# VCO.net
KiCad netlist of a schematic drawn in EAGLE
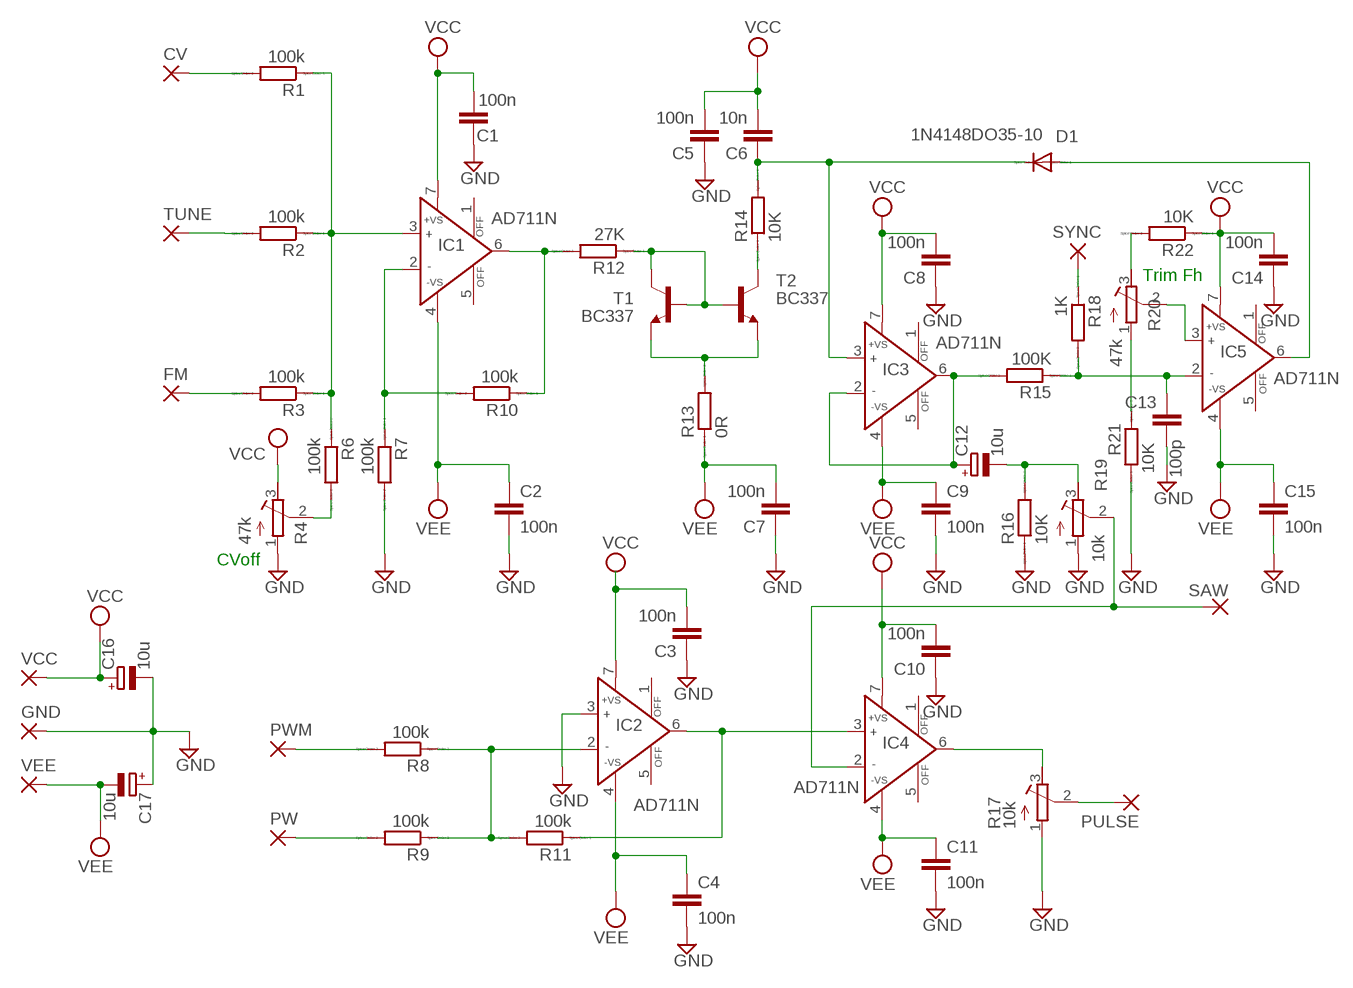
[diagram p0: schematic, sheet 1]

(export (version "E")
  (design (tool "Eeschema 10.0.6"))
  (components
    (comp (ref "C1")
      (value "100n")
      (footprint "eagle-import:C5B2.5")
      (libsource (lib "eagle-import") (part "C5/2.5"))
    )
    (comp (ref "C2")
      (value "100n")
      (footprint "eagle-import:C5B2.5")
      (libsource (lib "eagle-import") (part "C5/2.5"))
    )
    (comp (ref "C3")
      (value "100n")
      (footprint "eagle-import:C5B2.5")
      (libsource (lib "eagle-import") (part "C5/2.5"))
    )
    (comp (ref "C4")
      (value "100n")
      (footprint "eagle-import:C5B2.5")
      (libsource (lib "eagle-import") (part "C5/2.5"))
    )
    (comp (ref "C5")
      (value "100n")
      (footprint "eagle-import:C5B2.5")
      (libsource (lib "eagle-import") (part "C5/2.5"))
    )
    (comp (ref "C6")
      (value "10n")
      (footprint "eagle-import:C5B2.5")
      (libsource (lib "eagle-import") (part "C5/2.5"))
    )
    (comp (ref "C7")
      (value "100n")
      (footprint "eagle-import:C5B2.5")
      (libsource (lib "eagle-import") (part "C5/2.5"))
    )
    (comp (ref "C8")
      (value "100n")
      (footprint "eagle-import:C5B2.5")
      (libsource (lib "eagle-import") (part "C5/2.5"))
    )
    (comp (ref "C9")
      (value "100n")
      (footprint "eagle-import:C5B2.5")
      (libsource (lib "eagle-import") (part "C5/2.5"))
    )
    (comp (ref "C10")
      (value "100n")
      (footprint "eagle-import:C5B2.5")
      (libsource (lib "eagle-import") (part "C5/2.5"))
    )
    (comp (ref "C11")
      (value "100n")
      (footprint "eagle-import:C5B2.5")
      (libsource (lib "eagle-import") (part "C5/2.5"))
    )
    (comp (ref "C12")
      (value "10u")
      (footprint "eagle-import:E2,5-7")
      (libsource (lib "eagle-import") (part "CPOL-EUE2.5-7"))
    )
    (comp (ref "C13")
      (value "100p")
      (footprint "eagle-import:C2.5-2")
      (libsource (lib "eagle-import") (part "C2.5/2"))
    )
    (comp (ref "C14")
      (value "100n")
      (footprint "eagle-import:C5B2.5")
      (libsource (lib "eagle-import") (part "C5/2.5"))
    )
    (comp (ref "C15")
      (value "100n")
      (footprint "eagle-import:C5B2.5")
      (libsource (lib "eagle-import") (part "C5/2.5"))
    )
    (comp (ref "C16")
      (value "10u")
      (footprint "eagle-import:E2,5-7")
      (libsource (lib "eagle-import") (part "CPOL-EUE2.5-7"))
    )
    (comp (ref "C17")
      (value "10u")
      (footprint "eagle-import:E2,5-7")
      (libsource (lib "eagle-import") (part "CPOL-EUE2.5-7"))
    )
    (comp (ref "CV")
      (value "3,17/1,1")
      (footprint "eagle-import:3,17_1,1")
      (libsource (lib "eagle-import") (part "3,17/1,1"))
    )
    (comp (ref "D1")
      (value "1N4148DO35-10")
      (footprint "eagle-import:DO35-10")
      (libsource (lib "eagle-import") (part "1N4148DO35-10"))
    )
    (comp (ref "FM")
      (value "3,17/1,1")
      (footprint "eagle-import:3,17_1,1")
      (libsource (lib "eagle-import") (part "3,17/1,1"))
    )
    (comp (ref "GND")
      (value "3,17/1,1")
      (footprint "eagle-import:3,17_1,1")
      (libsource (lib "eagle-import") (part "3,17/1,1"))
    )
    (comp (ref "IC1")
      (value "AD711N")
      (footprint "eagle-import:DIL08")
      (fields (field (name "MPN") "AD711BQ"))
      (libsource (lib "eagle-import") (part "AD711N"))
    )
    (comp (ref "IC2")
      (value "AD711N")
      (footprint "eagle-import:DIL08")
      (fields (field (name "MPN") "AD711BQ"))
      (libsource (lib "eagle-import") (part "AD711N"))
    )
    (comp (ref "IC3")
      (value "AD711N")
      (footprint "eagle-import:DIL08")
      (fields (field (name "MPN") "AD711BQ"))
      (libsource (lib "eagle-import") (part "AD711N"))
    )
    (comp (ref "IC4")
      (value "AD711N")
      (footprint "eagle-import:DIL08")
      (fields (field (name "MPN") "AD711BQ"))
      (libsource (lib "eagle-import") (part "AD711N"))
    )
    (comp (ref "IC5")
      (value "AD711N")
      (footprint "eagle-import:DIL08")
      (fields (field (name "MPN") "AD711BQ"))
      (libsource (lib "eagle-import") (part "AD711N"))
    )
    (comp (ref "PULSE")
      (value "3,17/1,1")
      (footprint "eagle-import:3,17_1,1")
      (libsource (lib "eagle-import") (part "3,17/1,1"))
    )
    (comp (ref "PW")
      (value "3,17/1,1")
      (footprint "eagle-import:3,17_1,1")
      (libsource (lib "eagle-import") (part "3,17/1,1"))
    )
    (comp (ref "PWM")
      (value "3,17/1,1")
      (footprint "eagle-import:3,17_1,1")
      (libsource (lib "eagle-import") (part "3,17/1,1"))
    )
    (comp (ref "R1")
      (value "100k")
      (footprint "eagle-import:0207_10")
      (fields (field (name "SPICEPREFIX") "27K"))
      (libsource (lib "eagle-import") (part "R0207/10"))
    )
    (comp (ref "R2")
      (value "100k")
      (footprint "eagle-import:0207_10")
      (fields (field (name "SPICEPREFIX") "27K"))
      (libsource (lib "eagle-import") (part "R0207/10"))
    )
    (comp (ref "R3")
      (value "100k")
      (footprint "eagle-import:0207_10")
      (fields (field (name "SPICEPREFIX") "27K"))
      (libsource (lib "eagle-import") (part "R0207/10"))
    )
    (comp (ref "R4")
      (value "47k")
      (footprint "eagle-import:RTRIM64W")
      (libsource (lib "eagle-import") (part "R-TRIMM64W"))
    )
    (comp (ref "R6")
      (value "100k")
      (footprint "eagle-import:0207_10")
      (fields (field (name "SPICEPREFIX") "27K"))
      (libsource (lib "eagle-import") (part "R0207/10"))
    )
    (comp (ref "R7")
      (value "100k")
      (footprint "eagle-import:0207_10")
      (fields (field (name "SPICEPREFIX") "27K"))
      (libsource (lib "eagle-import") (part "R0207/10"))
    )
    (comp (ref "R8")
      (value "100k")
      (footprint "eagle-import:0207_10")
      (fields (field (name "SPICEPREFIX") "27K"))
      (libsource (lib "eagle-import") (part "R0207/10"))
    )
    (comp (ref "R9")
      (value "100k")
      (footprint "eagle-import:0207_10")
      (fields (field (name "SPICEPREFIX") "27K"))
      (libsource (lib "eagle-import") (part "R0207/10"))
    )
    (comp (ref "R10")
      (value "100k")
      (footprint "eagle-import:0207_10")
      (fields (field (name "SPICEPREFIX") "27K"))
      (libsource (lib "eagle-import") (part "R0207/10"))
    )
    (comp (ref "R11")
      (value "100k")
      (footprint "eagle-import:0207_10")
      (fields (field (name "SPICEPREFIX") "27K"))
      (libsource (lib "eagle-import") (part "R0207/10"))
    )
    (comp (ref "R12")
      (value "27K")
      (footprint "eagle-import:0207_10")
      (fields (field (name "SPICEPREFIX") "27K"))
      (libsource (lib "eagle-import") (part "R0207/10"))
    )
    (comp (ref "R13")
      (value "0R")
      (footprint "eagle-import:0207_10")
      (libsource (lib "eagle-import") (part "R0207/10"))
    )
    (comp (ref "R14")
      (value "10K")
      (footprint "eagle-import:0207_10")
      (fields (field (name "SPICEPREFIX") "10K"))
      (libsource (lib "eagle-import") (part "R0207/10"))
    )
    (comp (ref "R15")
      (value "100K")
      (footprint "eagle-import:0207_10")
      (libsource (lib "eagle-import") (part "R0207/10"))
    )
    (comp (ref "R16")
      (value "10K")
      (footprint "eagle-import:0207_10")
      (fields (field (name "SPICEPREFIX") "10K"))
      (libsource (lib "eagle-import") (part "R0207/10"))
    )
    (comp (ref "R17")
      (value "10k")
      (footprint "eagle-import:RTRIM3339P")
      (libsource (lib "eagle-import") (part "resistor_R-TRIMM3339P"))
    )
    (comp (ref "R18")
      (value "1K")
      (footprint "eagle-import:0207_10")
      (libsource (lib "eagle-import") (part "R0207/10"))
    )
    (comp (ref "R19")
      (value "10k")
      (footprint "eagle-import:RTRIM3339P")
      (libsource (lib "eagle-import") (part "resistor_R-TRIMM3339P"))
    )
    (comp (ref "R20")
      (value "47k")
      (footprint "eagle-import:RTRIM64W")
      (libsource (lib "eagle-import") (part "R-TRIMM64W"))
    )
    (comp (ref "R21")
      (value "10K")
      (footprint "eagle-import:0207_10")
      (fields (field (name "SPICEPREFIX") "10K"))
      (libsource (lib "eagle-import") (part "R0207/10"))
    )
    (comp (ref "R22")
      (value "10K")
      (footprint "eagle-import:0207_10")
      (fields (field (name "SPICEPREFIX") "10K"))
      (libsource (lib "eagle-import") (part "R0207/10"))
    )
    (comp (ref "SAW")
      (value "3,17/1,1")
      (footprint "eagle-import:3,17_1,1")
      (libsource (lib "eagle-import") (part "3,17/1,1"))
    )
    (comp (ref "SYNC")
      (value "3,17/1,1")
      (footprint "eagle-import:3,17_1,1")
      (libsource (lib "eagle-import") (part "3,17/1,1"))
    )
    (comp (ref "T1")
      (value "BC337")
      (footprint "eagle-import:TO92")
      (libsource (lib "eagle-import") (part "BC337"))
    )
    (comp (ref "T2")
      (value "BC337")
      (footprint "eagle-import:TO92")
      (libsource (lib "eagle-import") (part "BC337"))
    )
    (comp (ref "TUNE")
      (value "3,17/1,1")
      (footprint "eagle-import:3,17_1,1")
      (libsource (lib "eagle-import") (part "3,17/1,1"))
    )
    (comp (ref "VCC")
      (value "3,17/1,1")
      (footprint "eagle-import:3,17_1,1")
      (libsource (lib "eagle-import") (part "3,17/1,1"))
    )
    (comp (ref "VEE")
      (value "3,17/1,1")
      (footprint "eagle-import:3,17_1,1")
      (libsource (lib "eagle-import") (part "3,17/1,1"))
    )
  )
  (nets
    (net (code "1") (name "GND") (class "Default")
      (node (ref "C1") (pin "1") (pinfunction "1_1") (pintype "passive"))
      (node (ref "C10") (pin "1") (pinfunction "1_1") (pintype "passive"))
      (node (ref "C11") (pin "2") (pinfunction "2_2") (pintype "passive"))
      (node (ref "C13") (pin "1") (pinfunction "1_1") (pintype "passive"))
      (node (ref "C14") (pin "1") (pinfunction "1_1") (pintype "passive"))
      (node (ref "C15") (pin "2") (pinfunction "2_2") (pintype "passive"))
      (node (ref "C16") (pin "-") (pinfunction "-_-") (pintype "passive"))
      (node (ref "C17") (pin "+") (pinfunction "+_+") (pintype "passive"))
      (node (ref "C2") (pin "2") (pinfunction "2_2") (pintype "passive"))
      (node (ref "C3") (pin "1") (pinfunction "1_1") (pintype "passive"))
      (node (ref "C4") (pin "2") (pinfunction "2_2") (pintype "passive"))
      (node (ref "C5") (pin "1") (pinfunction "1_1") (pintype "passive"))
      (node (ref "C7") (pin "1") (pinfunction "1_1") (pintype "passive"))
      (node (ref "C8") (pin "1") (pinfunction "1_1") (pintype "passive"))
      (node (ref "C9") (pin "2") (pinfunction "2_2") (pintype "passive"))
      (node (ref "GND") (pin "1") (pinfunction "P_1") (pintype "passive"))
      (node (ref "IC2") (pin "3") (pinfunction "IN+_3") (pintype "input"))
      (node (ref "R16") (pin "1") (pinfunction "1_1") (pintype "passive"))
      (node (ref "R17") (pin "1") (pinfunction "A_1") (pintype "passive"))
      (node (ref "R19") (pin "1") (pinfunction "A_1") (pintype "passive"))
      (node (ref "R21") (pin "1") (pinfunction "1_1") (pintype "passive"))
      (node (ref "R4") (pin "1") (pinfunction "A_1") (pintype "passive"))
      (node (ref "R7") (pin "2") (pinfunction "2_2") (pintype "passive"))
    )
    (net (code "2") (name "Net-(CV-P)") (class "Default")
      (node (ref "CV") (pin "1") (pinfunction "P_1") (pintype "passive"))
      (node (ref "R1") (pin "2") (pinfunction "2_2") (pintype "passive"))
    )
    (net (code "3") (name "Net-(FM-P)") (class "Default")
      (node (ref "FM") (pin "1") (pinfunction "P_1") (pintype "passive"))
      (node (ref "R3") (pin "2") (pinfunction "2_2") (pintype "passive"))
    )
    (net (code "4") (name "Net-(IC1-IN+)") (class "Default")
      (node (ref "IC1") (pin "3") (pinfunction "IN+_3") (pintype "input"))
      (node (ref "R1") (pin "1") (pinfunction "1_1") (pintype "passive"))
      (node (ref "R2") (pin "1") (pinfunction "1_1") (pintype "passive"))
      (node (ref "R3") (pin "1") (pinfunction "1_1") (pintype "passive"))
      (node (ref "R6") (pin "1") (pinfunction "1_1") (pintype "passive"))
    )
    (net (code "5") (name "Net-(IC1-IN-)") (class "Default")
      (node (ref "IC1") (pin "2") (pinfunction "IN-_2") (pintype "input"))
      (node (ref "R10") (pin "2") (pinfunction "2_2") (pintype "passive"))
      (node (ref "R7") (pin "1") (pinfunction "1_1") (pintype "passive"))
    )
    (net (code "6") (name "Net-(IC1-OUT)") (class "Default")
      (node (ref "IC1") (pin "6") (pinfunction "OUT_6") (pintype "output"))
      (node (ref "R10") (pin "1") (pinfunction "1_1") (pintype "passive"))
      (node (ref "R12") (pin "2") (pinfunction "2_2") (pintype "passive"))
    )
    (net (code "7") (name "Net-(IC2-IN-)") (class "Default")
      (node (ref "IC2") (pin "2") (pinfunction "IN-_2") (pintype "input"))
      (node (ref "R11") (pin "2") (pinfunction "2_2") (pintype "passive"))
      (node (ref "R8") (pin "1") (pinfunction "1_1") (pintype "passive"))
      (node (ref "R9") (pin "1") (pinfunction "1_1") (pintype "passive"))
    )
    (net (code "8") (name "Net-(IC2-OUT)") (class "Default")
      (node (ref "IC2") (pin "6") (pinfunction "OUT_6") (pintype "output"))
      (node (ref "IC4") (pin "3") (pinfunction "IN+_3") (pintype "input"))
      (node (ref "R11") (pin "1") (pinfunction "1_1") (pintype "passive"))
    )
    (net (code "9") (name "Net-(IC3-IN+)") (class "Default")
      (node (ref "C6") (pin "1") (pinfunction "1_1") (pintype "passive"))
      (node (ref "D1") (pin "C") (pinfunction "C_C") (pintype "passive"))
      (node (ref "IC3") (pin "3") (pinfunction "IN+_3") (pintype "input"))
      (node (ref "R14") (pin "2") (pinfunction "2_2") (pintype "passive"))
    )
    (net (code "10") (name "Net-(IC3-IN-)") (class "Default")
      (node (ref "C12") (pin "+") (pinfunction "+_+") (pintype "passive"))
      (node (ref "IC3") (pin "2") (pinfunction "IN-_2") (pintype "input"))
      (node (ref "IC3") (pin "6") (pinfunction "OUT_6") (pintype "output"))
      (node (ref "R15") (pin "2") (pinfunction "2_2") (pintype "passive"))
    )
    (net (code "11") (name "Net-(IC4-IN-)") (class "Default")
      (node (ref "IC4") (pin "2") (pinfunction "IN-_2") (pintype "input"))
      (node (ref "R19") (pin "2") (pinfunction "S_2") (pintype "passive"))
      (node (ref "SAW") (pin "1") (pinfunction "P_1") (pintype "passive"))
    )
    (net (code "12") (name "Net-(IC4-OUT)") (class "Default")
      (node (ref "IC4") (pin "6") (pinfunction "OUT_6") (pintype "output"))
      (node (ref "R17") (pin "3") (pinfunction "E_3") (pintype "passive"))
    )
    (net (code "13") (name "Net-(IC5-IN+)") (class "Default")
      (node (ref "IC5") (pin "3") (pinfunction "IN+_3") (pintype "input"))
      (node (ref "R20") (pin "2") (pinfunction "S_2") (pintype "passive"))
    )
    (net (code "14") (name "Net-(IC5-IN-)") (class "Default")
      (node (ref "C13") (pin "2") (pinfunction "2_2") (pintype "passive"))
      (node (ref "IC5") (pin "2") (pinfunction "IN-_2") (pintype "input"))
      (node (ref "R15") (pin "1") (pinfunction "1_1") (pintype "passive"))
      (node (ref "R18") (pin "2") (pinfunction "2_2") (pintype "passive"))
    )
    (net (code "15") (name "Net-(IC5-OUT)") (class "Default")
      (node (ref "D1") (pin "A") (pinfunction "A_A") (pintype "passive"))
      (node (ref "IC5") (pin "6") (pinfunction "OUT_6") (pintype "output"))
    )
    (net (code "16") (name "Net-(PULSE-P)") (class "Default")
      (node (ref "PULSE") (pin "1") (pinfunction "P_1") (pintype "passive"))
      (node (ref "R17") (pin "2") (pinfunction "S_2") (pintype "passive"))
    )
    (net (code "17") (name "Net-(PW-P)") (class "Default")
      (node (ref "PW") (pin "1") (pinfunction "P_1") (pintype "passive"))
      (node (ref "R9") (pin "2") (pinfunction "2_2") (pintype "passive"))
    )
    (net (code "18") (name "Net-(PWM-P)") (class "Default")
      (node (ref "PWM") (pin "1") (pinfunction "P_1") (pintype "passive"))
      (node (ref "R8") (pin "2") (pinfunction "2_2") (pintype "passive"))
    )
    (net (code "19") (name "Net-(R4-S)") (class "Default")
      (node (ref "R4") (pin "2") (pinfunction "S_2") (pintype "passive"))
      (node (ref "R6") (pin "2") (pinfunction "2_2") (pintype "passive"))
    )
    (net (code "20") (name "Net-(R19-E)") (class "Default")
      (node (ref "C12") (pin "-") (pinfunction "-_-") (pintype "passive"))
      (node (ref "R16") (pin "2") (pinfunction "2_2") (pintype "passive"))
      (node (ref "R19") (pin "3") (pinfunction "E_3") (pintype "passive"))
    )
    (net (code "21") (name "Net-(R20-A)") (class "Default")
      (node (ref "R20") (pin "1") (pinfunction "A_1") (pintype "passive"))
      (node (ref "R21") (pin "2") (pinfunction "2_2") (pintype "passive"))
    )
    (net (code "22") (name "Net-(R20-E)") (class "Default")
      (node (ref "R20") (pin "3") (pinfunction "E_3") (pintype "passive"))
      (node (ref "R22") (pin "2") (pinfunction "2_2") (pintype "passive"))
    )
    (net (code "23") (name "Net-(SYNC-P)") (class "Default")
      (node (ref "R18") (pin "1") (pinfunction "1_1") (pintype "passive"))
      (node (ref "SYNC") (pin "1") (pinfunction "P_1") (pintype "passive"))
    )
    (net (code "24") (name "Net-(T1-B)") (class "Default")
      (node (ref "R12") (pin "1") (pinfunction "1_1") (pintype "passive"))
      (node (ref "T1") (pin "2") (pinfunction "B_2") (pintype "passive"))
      (node (ref "T1") (pin "3") (pinfunction "C_3") (pintype "passive"))
      (node (ref "T2") (pin "2") (pinfunction "B_2") (pintype "passive"))
    )
    (net (code "25") (name "Net-(T1-E)") (class "Default")
      (node (ref "R13") (pin "2") (pinfunction "2_2") (pintype "passive"))
      (node (ref "T1") (pin "1") (pinfunction "E_1") (pintype "passive"))
      (node (ref "T2") (pin "1") (pinfunction "E_1") (pintype "passive"))
    )
    (net (code "26") (name "Net-(T2-C)") (class "Default")
      (node (ref "R14") (pin "1") (pinfunction "1_1") (pintype "passive"))
      (node (ref "T2") (pin "3") (pinfunction "C_3") (pintype "passive"))
    )
    (net (code "27") (name "Net-(TUNE-P)") (class "Default")
      (node (ref "R2") (pin "2") (pinfunction "2_2") (pintype "passive"))
      (node (ref "TUNE") (pin "1") (pinfunction "P_1") (pintype "passive"))
    )
    (net (code "28") (name "VCC") (class "Default")
      (node (ref "C1") (pin "2") (pinfunction "2_2") (pintype "passive"))
      (node (ref "C10") (pin "2") (pinfunction "2_2") (pintype "passive"))
      (node (ref "C14") (pin "2") (pinfunction "2_2") (pintype "passive"))
      (node (ref "C16") (pin "+") (pinfunction "+_+") (pintype "passive"))
      (node (ref "C3") (pin "2") (pinfunction "2_2") (pintype "passive"))
      (node (ref "C5") (pin "2") (pinfunction "2_2") (pintype "passive"))
      (node (ref "C6") (pin "2") (pinfunction "2_2") (pintype "passive"))
      (node (ref "C8") (pin "2") (pinfunction "2_2") (pintype "passive"))
      (node (ref "IC1") (pin "7") (pinfunction "+VS_7") (pintype "input"))
      (node (ref "IC2") (pin "7") (pinfunction "+VS_7") (pintype "input"))
      (node (ref "IC3") (pin "7") (pinfunction "+VS_7") (pintype "input"))
      (node (ref "IC4") (pin "7") (pinfunction "+VS_7") (pintype "input"))
      (node (ref "IC5") (pin "7") (pinfunction "+VS_7") (pintype "input"))
      (node (ref "R22") (pin "1") (pinfunction "1_1") (pintype "passive"))
      (node (ref "R4") (pin "3") (pinfunction "E_3") (pintype "passive"))
      (node (ref "VCC") (pin "1") (pinfunction "P_1") (pintype "passive"))
    )
    (net (code "29") (name "VEE") (class "Default")
      (node (ref "C11") (pin "1") (pinfunction "1_1") (pintype "passive"))
      (node (ref "C15") (pin "1") (pinfunction "1_1") (pintype "passive"))
      (node (ref "C17") (pin "-") (pinfunction "-_-") (pintype "passive"))
      (node (ref "C2") (pin "1") (pinfunction "1_1") (pintype "passive"))
      (node (ref "C4") (pin "1") (pinfunction "1_1") (pintype "passive"))
      (node (ref "C7") (pin "2") (pinfunction "2_2") (pintype "passive"))
      (node (ref "C9") (pin "1") (pinfunction "1_1") (pintype "passive"))
      (node (ref "IC1") (pin "4") (pinfunction "-VS_4") (pintype "input"))
      (node (ref "IC2") (pin "4") (pinfunction "-VS_4") (pintype "input"))
      (node (ref "IC3") (pin "4") (pinfunction "-VS_4") (pintype "input"))
      (node (ref "IC4") (pin "4") (pinfunction "-VS_4") (pintype "input"))
      (node (ref "IC5") (pin "4") (pinfunction "-VS_4") (pintype "input"))
      (node (ref "R13") (pin "1") (pinfunction "1_1") (pintype "passive"))
      (node (ref "VEE") (pin "1") (pinfunction "P_1") (pintype "passive"))
    )
    (net (code "30") (name "unconnected-(IC1-OFF-Pad1)") (class "Default")
      (node (ref "IC1") (pin "1") (pinfunction "OFF_1") (pintype "passive"))
    )
    (net (code "31") (name "unconnected-(IC1-OFF-Pad5)") (class "Default")
      (node (ref "IC1") (pin "5") (pinfunction "OFF_5") (pintype "passive"))
    )
    (net (code "32") (name "unconnected-(IC2-OFF-Pad1)") (class "Default")
      (node (ref "IC2") (pin "1") (pinfunction "OFF_1") (pintype "passive"))
    )
    (net (code "33") (name "unconnected-(IC2-OFF-Pad5)") (class "Default")
      (node (ref "IC2") (pin "5") (pinfunction "OFF_5") (pintype "passive"))
    )
    (net (code "34") (name "unconnected-(IC3-OFF-Pad1)") (class "Default")
      (node (ref "IC3") (pin "1") (pinfunction "OFF_1") (pintype "passive"))
    )
    (net (code "35") (name "unconnected-(IC3-OFF-Pad5)") (class "Default")
      (node (ref "IC3") (pin "5") (pinfunction "OFF_5") (pintype "passive"))
    )
    (net (code "36") (name "unconnected-(IC4-OFF-Pad1)") (class "Default")
      (node (ref "IC4") (pin "1") (pinfunction "OFF_1") (pintype "passive"))
    )
    (net (code "37") (name "unconnected-(IC4-OFF-Pad5)") (class "Default")
      (node (ref "IC4") (pin "5") (pinfunction "OFF_5") (pintype "passive"))
    )
    (net (code "38") (name "unconnected-(IC5-OFF-Pad1)") (class "Default")
      (node (ref "IC5") (pin "1") (pinfunction "OFF_1") (pintype "passive"))
    )
    (net (code "39") (name "unconnected-(IC5-OFF-Pad5)") (class "Default")
      (node (ref "IC5") (pin "5") (pinfunction "OFF_5") (pintype "passive"))
    )
  )
)
